# micro_power.net
KiCad netlist of a schematic drawn in Altium Designer
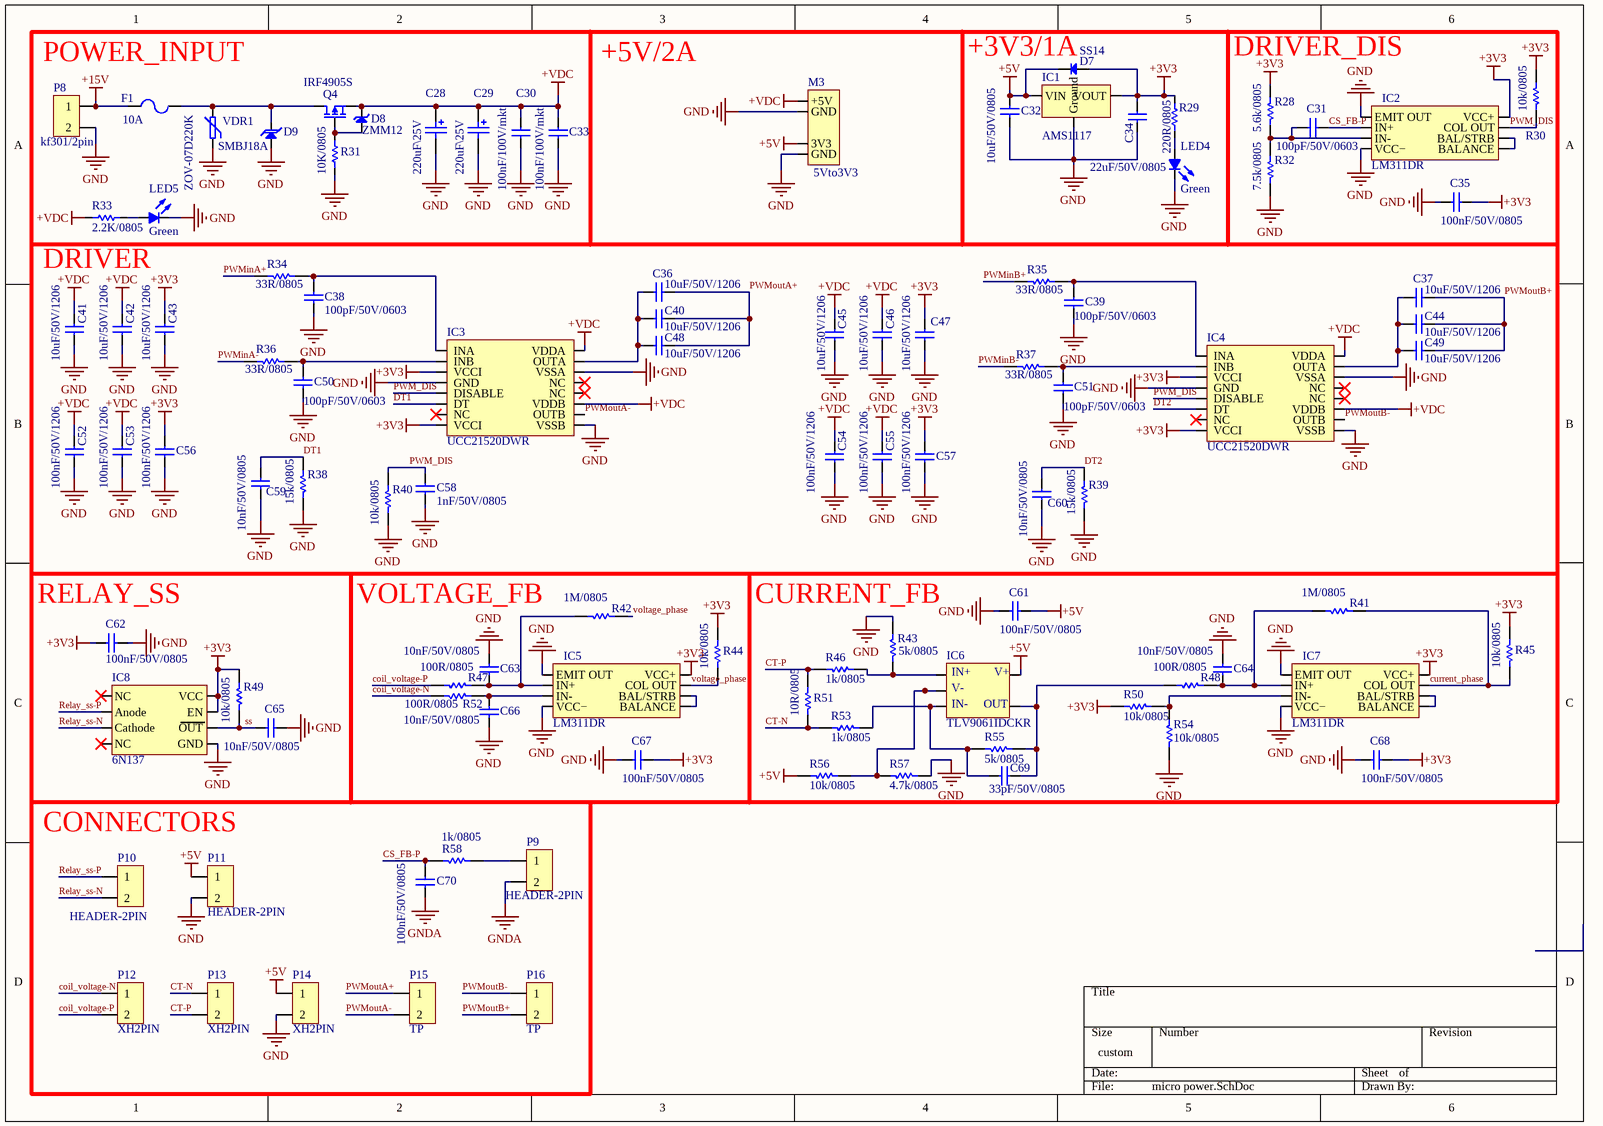
[diagram p0: micro power.SchDoc]

(export (version "E")
  (design (tool "Eeschema 10.0.6"))
  (components
    (comp (ref "C28")
      (value "220u~{F}25V")
      (footprint "cap 5*11,p=2")
      (description "Polarized Capacitor (Radial)")
      (fields (field (name "PUBLISHER") "Altium Limited"))
      (libsource (lib "Schlib") (part "Cap Pol1"))
    )
    (comp (ref "C29")
      (value "220u~{F}25V")
      (footprint "cap 5*11,p=2")
      (description "Polarized Capacitor (Radial)")
      (fields (field (name "PUBLISHER") "Altium Limited"))
      (libsource (lib "Schlib") (part "Cap Pol1"))
    )
    (comp (ref "C30")
      (value "100nF/100V/mkt")
      (footprint "mkt 5mm")
      (description "Capacitor")
      (libsource (lib "Schlib") (part "Capacitor"))
    )
    (comp (ref "C31")
      (value "100pF/50V/0603")
      (footprint "cap 0603")
      (description "Capacitor")
      (libsource (lib "Schlib") (part "Capacitor"))
    )
    (comp (ref "C32")
      (value "10uF/50V/0805")
      (footprint "CAP 0805")
      (description "Capacitor")
      (libsource (lib "Schlib") (part "Capacitor"))
    )
    (comp (ref "C33")
      (value "100nF/100V/mkt")
      (footprint "mkt 5mm")
      (description "Capacitor")
      (libsource (lib "Schlib") (part "Capacitor"))
    )
    (comp (ref "C34")
      (value "22uF/50V/0805")
      (footprint "CAP 0805")
      (description "Capacitor")
      (libsource (lib "Schlib") (part "Capacitor"))
    )
    (comp (ref "C35")
      (value "100nF/50V/0805")
      (footprint "CAP 0805")
      (description "Capacitor")
      (libsource (lib "Schlib") (part "Capacitor"))
    )
    (comp (ref "C36")
      (value "10uF/50V/1206")
      (footprint "CAP 1206")
      (description "Capacitor")
      (libsource (lib "Schlib") (part "Capacitor"))
    )
    (comp (ref "C37")
      (value "10uF/50V/1206")
      (footprint "CAP 1206")
      (description "Capacitor")
      (libsource (lib "Schlib") (part "Capacitor"))
    )
    (comp (ref "C38")
      (value "100pF/50V/0603")
      (footprint "cap 0603")
      (description "Capacitor")
      (libsource (lib "Schlib") (part "Capacitor"))
    )
    (comp (ref "C39")
      (value "100pF/50V/0603")
      (footprint "cap 0603")
      (description "Capacitor")
      (libsource (lib "Schlib") (part "Capacitor"))
    )
    (comp (ref "C40")
      (value "10uF/50V/1206")
      (footprint "CAP 1206")
      (description "Capacitor")
      (libsource (lib "Schlib") (part "Capacitor"))
    )
    (comp (ref "C41")
      (value "10uF/50V/1206")
      (footprint "CAP 1206")
      (description "Capacitor")
      (libsource (lib "Schlib") (part "Capacitor"))
    )
    (comp (ref "C42")
      (value "10uF/50V/1206")
      (footprint "CAP 1206")
      (description "Capacitor")
      (libsource (lib "Schlib") (part "Capacitor"))
    )
    (comp (ref "C43")
      (value "10uF/50V/1206")
      (footprint "CAP 1206")
      (description "Capacitor")
      (libsource (lib "Schlib") (part "Capacitor"))
    )
    (comp (ref "C44")
      (value "10uF/50V/1206")
      (footprint "CAP 1206")
      (description "Capacitor")
      (libsource (lib "Schlib") (part "Capacitor"))
    )
    (comp (ref "C45")
      (value "10uF/50V/1206")
      (footprint "CAP 1206")
      (description "Capacitor")
      (libsource (lib "Schlib") (part "Capacitor"))
    )
    (comp (ref "C46")
      (value "10uF/50V/1206")
      (footprint "CAP 1206")
      (description "Capacitor")
      (libsource (lib "Schlib") (part "Capacitor"))
    )
    (comp (ref "C47")
      (value "10uF/50V/1206")
      (footprint "CAP 1206")
      (description "Capacitor")
      (libsource (lib "Schlib") (part "Capacitor"))
    )
    (comp (ref "C48")
      (value "10uF/50V/1206")
      (footprint "CAP 1206")
      (description "Capacitor")
      (libsource (lib "Schlib") (part "Capacitor"))
    )
    (comp (ref "C49")
      (value "10uF/50V/1206")
      (footprint "CAP 1206")
      (description "Capacitor")
      (libsource (lib "Schlib") (part "Capacitor"))
    )
    (comp (ref "C50")
      (value "100pF/50V/0603")
      (footprint "cap 0603")
      (description "Capacitor")
      (libsource (lib "Schlib") (part "Capacitor"))
    )
    (comp (ref "C51")
      (value "100pF/50V/0603")
      (footprint "cap 0603")
      (description "Capacitor")
      (libsource (lib "Schlib") (part "Capacitor"))
    )
    (comp (ref "C52")
      (value "100nF/50V/1206")
      (footprint "CAP 1206")
      (description "Capacitor")
      (libsource (lib "Schlib") (part "Capacitor"))
    )
    (comp (ref "C53")
      (value "100nF/50V/1206")
      (footprint "CAP 1206")
      (description "Capacitor")
      (libsource (lib "Schlib") (part "Capacitor"))
    )
    (comp (ref "C54")
      (value "100nF/50V/1206")
      (footprint "CAP 1206")
      (description "Capacitor")
      (libsource (lib "Schlib") (part "Capacitor"))
    )
    (comp (ref "C55")
      (value "100nF/50V/1206")
      (footprint "CAP 1206")
      (description "Capacitor")
      (libsource (lib "Schlib") (part "Capacitor"))
    )
    (comp (ref "C56")
      (value "100nF/50V/1206")
      (footprint "CAP 1206")
      (description "Capacitor")
      (libsource (lib "Schlib") (part "Capacitor"))
    )
    (comp (ref "C57")
      (value "100nF/50V/1206")
      (footprint "CAP 1206")
      (description "Capacitor")
      (libsource (lib "Schlib") (part "Capacitor"))
    )
    (comp (ref "C58")
      (value "1nF/50V/0805")
      (footprint "CAP 0805")
      (description "Capacitor")
      (libsource (lib "Schlib") (part "Capacitor"))
    )
    (comp (ref "C59")
      (value "10nF/50V/0805")
      (footprint "CAP 0805")
      (description "Capacitor")
      (libsource (lib "Schlib") (part "Capacitor"))
    )
    (comp (ref "C60")
      (value "10nF/50V/0805")
      (footprint "CAP 0805")
      (description "Capacitor")
      (libsource (lib "Schlib") (part "Capacitor"))
    )
    (comp (ref "C61")
      (value "100nF/50V/0805")
      (footprint "CAP 0805")
      (description "Capacitor")
      (libsource (lib "Schlib") (part "Capacitor"))
    )
    (comp (ref "C62")
      (value "100nF/50V/0805")
      (footprint "CAP 0805")
      (description "Capacitor")
      (libsource (lib "Schlib") (part "Capacitor"))
    )
    (comp (ref "C63")
      (value "10nF/50V/0805")
      (footprint "CAP 0805")
      (description "Capacitor")
      (libsource (lib "Schlib") (part "Capacitor"))
    )
    (comp (ref "C64")
      (value "10nF/50V/0805")
      (footprint "CAP 0805")
      (description "Capacitor")
      (libsource (lib "Schlib") (part "Capacitor"))
    )
    (comp (ref "C65")
      (value "10nF/50V/0805")
      (footprint "CAP 0805")
      (description "Capacitor")
      (libsource (lib "Schlib") (part "Capacitor"))
    )
    (comp (ref "C66")
      (value "10nF/50V/0805")
      (footprint "CAP 0805")
      (description "Capacitor")
      (libsource (lib "Schlib") (part "Capacitor"))
    )
    (comp (ref "C67")
      (value "100nF/50V/0805")
      (footprint "CAP 0805")
      (description "Capacitor")
      (libsource (lib "Schlib") (part "Capacitor"))
    )
    (comp (ref "C68")
      (value "100nF/50V/0805")
      (footprint "CAP 0805")
      (description "Capacitor")
      (libsource (lib "Schlib") (part "Capacitor"))
    )
    (comp (ref "C69")
      (value "33pF/50V/0805")
      (footprint "CAP 0805")
      (description "Capacitor")
      (libsource (lib "Schlib") (part "Capacitor"))
    )
    (comp (ref "C70")
      (value "100nF/50V/0805")
      (footprint "CAP 0805")
      (description "Capacitor")
      (libsource (lib "Schlib") (part "Capacitor"))
    )
    (comp (ref "D7") (value "SS14") (footprint "SMA") (libsource (lib "Schlib") (part "Diode")))
    (comp (ref "D8") (value "ZMM12") (footprint "minimelf") (libsource (lib "Schlib") (part "ZENER")))
    (comp (ref "D9")
      (value "SMBJ18A")
      (footprint "SMB(DO-214AA)")
      (libsource (lib "Schlib") (part "TVS_Unidirectional"))
    )
    (comp (ref "F1")
      (value "10A")
      (footprint "smd Fuse Block 155 OMNI-BLOK")
      (description "Fuse")
      (libsource (lib "Fx7sam") (part "Fuse"))
    )
    (comp (ref "IC1")
      (value "AMS1117")
      (footprint "TO252 (DPAK) (Type TH)")
      (libsource (lib "Schlib") (part "AMS1117"))
    )
    (comp (ref "IC2") (value "LM311DR") (footprint "SOIC-8") (libsource (lib "Schlib") (part "LM311DR")))
    (comp (ref "IC3")
      (value "UCC21520DWR")
      (footprint "SOIC16W")
      (libsource (lib "Schlib") (part "UCC21520DWR"))
    )
    (comp (ref "IC4")
      (value "UCC21520DWR")
      (footprint "SOIC16W")
      (libsource (lib "Schlib") (part "UCC21520DWR"))
    )
    (comp (ref "IC5") (value "LM311DR") (footprint "SOIC-8") (libsource (lib "Schlib") (part "LM311DR")))
    (comp (ref "IC6")
      (value "TLV9061IDCKR")
      (footprint "SC70-5")
      (libsource (lib "Schlib") (part "TLV9061IDCKR"))
    )
    (comp (ref "IC7") (value "LM311DR") (footprint "SOIC-8") (libsource (lib "Schlib") (part "LM311DR")))
    (comp (ref "IC8") (value "6N137") (footprint "SMD-8 Gull Wing") (libsource (lib "Schlib") (part "6N137")))
    (comp (ref "LED4")
      (value "LED 3mm/Green")
      (footprint "LED 3mm")
      (description "Typical LED")
      (fields (field (name "COLOR") "Green"))
      (libsource (lib "TL494 12V-20A-KARA") (part "LED"))
    )
    (comp (ref "LED5")
      (value "LED 3mm/Green")
      (footprint "LED 3mm")
      (description "Typical LED")
      (fields (field (name "COLOR") "Green"))
      (libsource (lib "TL494 12V-20A-KARA") (part "LED"))
    )
    (comp (ref "M3") (value "5Vto3V3") (footprint "5Vto3V3") (libsource (lib "Schlib") (part "5Vto3V3")))
    (comp (ref "P8")
      (value "kf301/2pin")
      (footprint "KF301-5.0-2P")
      (description "RELAY")
      (fields (field (name "PUBLISHER") "Altium Limited"))
      (libsource (lib "") (part "Header 2H_1"))
    )
    (comp (ref "P9")
      (value "HEADER-2PIN")
      (footprint "pin-header 2*1")
      (description "RELAY")
      (fields (field (name "PUBLISHER") "Altium Limited"))
      (libsource (lib "Schlib") (part "Header 2H"))
    )
    (comp (ref "P10")
      (value "HEADER-2PIN")
      (footprint "XH-2Pin")
      (description "RELAY")
      (fields (field (name "PUBLISHER") "Altium Limited"))
      (libsource (lib "Schlib") (part "Header 2H"))
    )
    (comp (ref "P11")
      (value "HEADER-2PIN")
      (footprint "pin-header 2*1")
      (description "RELAY")
      (fields (field (name "PUBLISHER") "Altium Limited"))
      (libsource (lib "Schlib") (part "Header 2H"))
    )
    (comp (ref "P12")
      (value "XH2PIN")
      (footprint "XH-2Pin")
      (description "RELAY")
      (fields (field (name "PUBLISHER") "Altium Limited"))
      (libsource (lib "Schlib") (part "Header 2H"))
    )
    (comp (ref "P13")
      (value "XH2PIN")
      (footprint "XH-2Pin")
      (description "RELAY")
      (fields (field (name "PUBLISHER") "Altium Limited"))
      (libsource (lib "Schlib") (part "Header 2H"))
    )
    (comp (ref "P14")
      (value "XH2PIN")
      (footprint "XH-2Pin")
      (description "RELAY")
      (fields (field (name "PUBLISHER") "Altium Limited"))
      (libsource (lib "Schlib") (part "Header 2H"))
    )
    (comp (ref "P15")
      (value "TP")
      (footprint "puls")
      (description "RELAY")
      (fields (field (name "PUBLISHER") "Altium Limited"))
      (libsource (lib "Schlib") (part "Header 2H"))
    )
    (comp (ref "P16")
      (value "TP")
      (footprint "puls")
      (description "RELAY")
      (fields (field (name "PUBLISHER") "Altium Limited"))
      (libsource (lib "Schlib") (part "Header 2H"))
    )
    (comp (ref "Q4")
      (value "IRF4905S")
      (footprint "TO263AB (D2PAK)")
      (description "D2pak")
      (libsource (lib "Schlib") (part "Mosfet P-channel"))
    )
    (comp (ref "R28")
      (value "5.6k/0805")
      (footprint "RES 0805")
      (description "Resistor")
      (fields (field (name "PUBLISHER") "Altium Limited"))
      (libsource (lib "Miscellaneous Devices") (part "Res1"))
    )
    (comp (ref "R29") (value "220R/0805") (footprint "RES 0805") (libsource (lib "Schlib") (part "Res")))
    (comp (ref "R30")
      (value "10k/0805")
      (footprint "RES 0805")
      (description "Resistor")
      (fields (field (name "PUBLISHER") "Altium Limited"))
      (libsource (lib "Miscellaneous Devices") (part "Res1"))
    )
    (comp (ref "R31") (value "10K/0805") (footprint "RES 0805") (libsource (lib "Schlib") (part "Res")))
    (comp (ref "R32")
      (value "7.5k/0805")
      (footprint "RES 0805")
      (description "Resistor")
      (fields (field (name "PUBLISHER") "Altium Limited"))
      (libsource (lib "Miscellaneous Devices") (part "Res1"))
    )
    (comp (ref "R33") (value "2.2K/0805") (footprint "RES 0805") (libsource (lib "Schlib") (part "Res")))
    (comp (ref "R34")
      (value "33R/0805")
      (footprint "RES 0805")
      (description "Resistor")
      (fields (field (name "PUBLISHER") "Altium Limited"))
      (libsource (lib "Miscellaneous Devices") (part "Res1"))
    )
    (comp (ref "R35")
      (value "33R/0805")
      (footprint "RES 0805")
      (description "Resistor")
      (fields (field (name "PUBLISHER") "Altium Limited"))
      (libsource (lib "Miscellaneous Devices") (part "Res1"))
    )
    (comp (ref "R36")
      (value "33R/0805")
      (footprint "RES 0805")
      (description "Resistor")
      (fields (field (name "PUBLISHER") "Altium Limited"))
      (libsource (lib "Miscellaneous Devices") (part "Res1"))
    )
    (comp (ref "R37")
      (value "33R/0805")
      (footprint "RES 0805")
      (description "Resistor")
      (fields (field (name "PUBLISHER") "Altium Limited"))
      (libsource (lib "Miscellaneous Devices") (part "Res1"))
    )
    (comp (ref "R38")
      (value "15k/0805")
      (footprint "RES 0805")
      (description "Resistor")
      (fields (field (name "PUBLISHER") "Altium Limited"))
      (libsource (lib "Miscellaneous Devices") (part "Res1"))
    )
    (comp (ref "R39")
      (value "15k/0805")
      (footprint "RES 0805")
      (description "Resistor")
      (fields (field (name "PUBLISHER") "Altium Limited"))
      (libsource (lib "Miscellaneous Devices") (part "Res1"))
    )
    (comp (ref "R40")
      (value "10k/0805")
      (footprint "RES 0805")
      (description "Resistor")
      (fields (field (name "PUBLISHER") "Altium Limited"))
      (libsource (lib "Miscellaneous Devices") (part "Res1"))
    )
    (comp (ref "R41")
      (value "1M/0805")
      (footprint "RES 0805")
      (description "Resistor")
      (fields (field (name "PUBLISHER") "Altium Limited"))
      (libsource (lib "Miscellaneous Devices") (part "Res1"))
    )
    (comp (ref "R42")
      (value "1M/0805")
      (footprint "RES 0805")
      (description "Resistor")
      (fields (field (name "PUBLISHER") "Altium Limited"))
      (libsource (lib "Miscellaneous Devices") (part "Res1"))
    )
    (comp (ref "R43")
      (value "5k/0805")
      (footprint "RES 0805")
      (description "Resistor")
      (fields (field (name "PUBLISHER") "Altium Limited"))
      (libsource (lib "Miscellaneous Devices") (part "Res1"))
    )
    (comp (ref "R44")
      (value "10k/0805")
      (footprint "RES 0805")
      (description "Resistor")
      (fields (field (name "PUBLISHER") "Altium Limited"))
      (libsource (lib "Miscellaneous Devices") (part "Res1"))
    )
    (comp (ref "R45")
      (value "10k/0805")
      (footprint "RES 0805")
      (description "Resistor")
      (fields (field (name "PUBLISHER") "Altium Limited"))
      (libsource (lib "Miscellaneous Devices") (part "Res1"))
    )
    (comp (ref "R46")
      (value "1k/0805")
      (footprint "RES 0805")
      (description "Resistor")
      (fields (field (name "PUBLISHER") "Altium Limited"))
      (libsource (lib "Miscellaneous Devices") (part "Res1"))
    )
    (comp (ref "R47")
      (value "100R/0805")
      (footprint "RES 0805")
      (description "Resistor")
      (fields (field (name "PUBLISHER") "Altium Limited"))
      (libsource (lib "Miscellaneous Devices") (part "Res1"))
    )
    (comp (ref "R48")
      (value "100R/0805")
      (footprint "RES 0805")
      (description "Resistor")
      (fields (field (name "PUBLISHER") "Altium Limited"))
      (libsource (lib "Miscellaneous Devices") (part "Res1"))
    )
    (comp (ref "R49")
      (value "10k/0805")
      (footprint "RES 0805")
      (description "Resistor")
      (fields (field (name "PUBLISHER") "Altium Limited"))
      (libsource (lib "Miscellaneous Devices") (part "Res1"))
    )
    (comp (ref "R50")
      (value "10k/0805")
      (footprint "RES 0805")
      (description "Resistor")
      (fields (field (name "PUBLISHER") "Altium Limited"))
      (libsource (lib "Miscellaneous Devices") (part "Res1"))
    )
    (comp (ref "R51")
      (value "10R/0805")
      (footprint "RES 0805")
      (description "Resistor")
      (fields (field (name "PUBLISHER") "Altium Limited"))
      (libsource (lib "Miscellaneous Devices") (part "Res1"))
    )
    (comp (ref "R52")
      (value "100R/0805")
      (footprint "RES 0805")
      (description "Resistor")
      (fields (field (name "PUBLISHER") "Altium Limited"))
      (libsource (lib "Miscellaneous Devices") (part "Res1"))
    )
    (comp (ref "R53")
      (value "1k/0805")
      (footprint "RES 0805")
      (description "Resistor")
      (fields (field (name "PUBLISHER") "Altium Limited"))
      (libsource (lib "Miscellaneous Devices") (part "Res1"))
    )
    (comp (ref "R54")
      (value "10k/0805")
      (footprint "RES 0805")
      (description "Resistor")
      (fields (field (name "PUBLISHER") "Altium Limited"))
      (libsource (lib "Miscellaneous Devices") (part "Res1"))
    )
    (comp (ref "R55")
      (value "5k/0805")
      (footprint "RES 0805")
      (description "Resistor")
      (fields (field (name "PUBLISHER") "Altium Limited"))
      (libsource (lib "Miscellaneous Devices") (part "Res1"))
    )
    (comp (ref "R56")
      (value "10k/0805")
      (footprint "RES 0805")
      (description "Resistor")
      (fields (field (name "PUBLISHER") "Altium Limited"))
      (libsource (lib "Miscellaneous Devices") (part "Res1"))
    )
    (comp (ref "R57")
      (value "4.7k/0805")
      (footprint "RES 0805")
      (description "Resistor")
      (fields (field (name "PUBLISHER") "Altium Limited"))
      (libsource (lib "Miscellaneous Devices") (part "Res1"))
    )
    (comp (ref "R58")
      (value "1k/0805")
      (footprint "RES 0805")
      (description "Resistor")
      (fields (field (name "PUBLISHER") "Altium Limited"))
      (libsource (lib "Miscellaneous Devices") (part "Res1"))
    )
    (comp (ref "VDR1")
      (value "ZOV-07D220K")
      (footprint "7D471K")
      (description "VARISTORS")
      (fields
        (field (name "MANUFACTURER") "china-canada-philipina")
        (field (name "DESIGNER") "Abbas Basereh")
        (field (name "PUBLISHER") "ABBAS BASEREH")
      )
      (libsource (lib "Schlib") (part "VARISTOR (VDR)"))
    )
  )
  (nets
    (net (code "1") (name "+3V3") (class "Default")
      (node (ref "C34") (pin "1") (pinfunction "+_1") (pintype "passive"))
      (node (ref "C35") (pin "1") (pinfunction "+_1") (pintype "passive"))
      (node (ref "C43") (pin "2") (pinfunction "-_2") (pintype "passive"))
      (node (ref "C47") (pin "2") (pinfunction "-_2") (pintype "passive"))
      (node (ref "C56") (pin "2") (pinfunction "-_2") (pintype "passive"))
      (node (ref "C57") (pin "2") (pinfunction "-_2") (pintype "passive"))
      (node (ref "C62") (pin "1") (pinfunction "+_1") (pintype "passive"))
      (node (ref "C67") (pin "1") (pinfunction "+_1") (pintype "passive"))
      (node (ref "C68") (pin "1") (pinfunction "+_1") (pintype "passive"))
      (node (ref "D7") (pin "1") (pinfunction "1_1") (pintype "passive"))
      (node (ref "IC1") (pin "2") (pinfunction "VOUT_2") (pintype "passive"))
      (node (ref "IC2") (pin "8") (pinfunction "VCC+_8") (pintype "passive"))
      (node (ref "IC3") (pin "3") (pinfunction "VCCI_3") (pintype "passive"))
      (node (ref "IC3") (pin "8") (pinfunction "VCCI_8") (pintype "passive"))
      (node (ref "IC4") (pin "3") (pinfunction "VCCI_3") (pintype "passive"))
      (node (ref "IC4") (pin "8") (pinfunction "VCCI_8") (pintype "passive"))
      (node (ref "IC5") (pin "8") (pinfunction "VCC+_8") (pintype "passive"))
      (node (ref "IC7") (pin "8") (pinfunction "VCC+_8") (pintype "passive"))
      (node (ref "IC8") (pin "7") (pinfunction "EN_7") (pintype "passive"))
      (node (ref "IC8") (pin "8") (pinfunction "VCC_8") (pintype "passive"))
      (node (ref "R28") (pin "2") (pinfunction "2_2") (pintype "passive"))
      (node (ref "R29") (pin "2") (pinfunction "2_2") (pintype "passive"))
      (node (ref "R30") (pin "2") (pinfunction "2_2") (pintype "passive"))
      (node (ref "R44") (pin "2") (pinfunction "2_2") (pintype "passive"))
      (node (ref "R45") (pin "2") (pinfunction "2_2") (pintype "passive"))
      (node (ref "R49") (pin "2") (pinfunction "2_2") (pintype "passive"))
      (node (ref "R50") (pin "2") (pinfunction "2_2") (pintype "passive"))
    )
    (net (code "2") (name "+5V") (class "Default")
      (node (ref "C32") (pin "1") (pinfunction "+_1") (pintype "passive"))
      (node (ref "C61") (pin "1") (pinfunction "+_1") (pintype "passive"))
      (node (ref "D7") (pin "2") (pinfunction "2_2") (pintype "passive"))
      (node (ref "IC1") (pin "3") (pinfunction "VIN_3") (pintype "passive"))
      (node (ref "IC6") (pin "5") (pinfunction "5_5") (pintype "passive"))
      (node (ref "M3") (pin "3") (pinfunction "3V3_3") (pintype "passive"))
      (node (ref "P11") (pin "1") (pinfunction "1_1") (pintype "passive"))
      (node (ref "P14") (pin "1") (pinfunction "1_1") (pintype "passive"))
      (node (ref "R56") (pin "1") (pinfunction "1_1") (pintype "passive"))
    )
    (net (code "3") (name "+15V") (class "Default")
      (node (ref "F1") (pin "1") (pinfunction "1_1") (pintype "passive"))
      (node (ref "P8") (pin "1") (pinfunction "1_1") (pintype "passive"))
    )
    (net (code "4") (name "+VDC") (class "Default")
      (node (ref "C28") (pin "1") (pinfunction "1_1") (pintype "passive"))
      (node (ref "C29") (pin "1") (pinfunction "1_1") (pintype "passive"))
      (node (ref "C30") (pin "1") (pinfunction "+_1") (pintype "passive"))
      (node (ref "C33") (pin "1") (pinfunction "+_1") (pintype "passive"))
      (node (ref "C41") (pin "2") (pinfunction "-_2") (pintype "passive"))
      (node (ref "C42") (pin "2") (pinfunction "-_2") (pintype "passive"))
      (node (ref "C45") (pin "2") (pinfunction "-_2") (pintype "passive"))
      (node (ref "C46") (pin "2") (pinfunction "-_2") (pintype "passive"))
      (node (ref "C52") (pin "2") (pinfunction "-_2") (pintype "passive"))
      (node (ref "C53") (pin "2") (pinfunction "-_2") (pintype "passive"))
      (node (ref "C54") (pin "2") (pinfunction "-_2") (pintype "passive"))
      (node (ref "C55") (pin "2") (pinfunction "-_2") (pintype "passive"))
      (node (ref "D8") (pin "2") (pinfunction "K_2") (pintype "passive"))
      (node (ref "IC3") (pin "11") (pinfunction "VDDB_11") (pintype "passive"))
      (node (ref "IC3") (pin "16") (pinfunction "VDDA_16") (pintype "passive"))
      (node (ref "IC4") (pin "11") (pinfunction "VDDB_11") (pintype "passive"))
      (node (ref "IC4") (pin "16") (pinfunction "VDDA_16") (pintype "passive"))
      (node (ref "M3") (pin "1") (pinfunction "+5V_1") (pintype "passive"))
      (node (ref "Q4") (pin "3") (pinfunction "S_3") (pintype "passive"))
      (node (ref "R33") (pin "2") (pinfunction "2_2") (pintype "passive"))
    )
    (net (code "5") (name "/CS_FB-P") (class "Default")
      (node (ref "C31") (pin "2") (pinfunction "-_2") (pintype "passive"))
      (node (ref "C70") (pin "1") (pinfunction "+_1") (pintype "passive"))
      (node (ref "IC2") (pin "2") (pinfunction "IN+_2") (pintype "passive"))
      (node (ref "R58") (pin "2") (pinfunction "2_2") (pintype "passive"))
    )
    (net (code "6") (name "/CT-N") (class "Default")
      (node (ref "P13") (pin "1") (pinfunction "1_1") (pintype "passive"))
      (node (ref "R51") (pin "1") (pinfunction "1_1") (pintype "passive"))
      (node (ref "R53") (pin "2") (pinfunction "2_2") (pintype "passive"))
    )
    (net (code "7") (name "/CT-P") (class "Default")
      (node (ref "P13") (pin "2") (pinfunction "2_2") (pintype "passive"))
      (node (ref "R46") (pin "2") (pinfunction "2_2") (pintype "passive"))
      (node (ref "R51") (pin "2") (pinfunction "2_2") (pintype "passive"))
    )
    (net (code "8") (name "/DT1") (class "Default")
      (node (ref "C59") (pin "2") (pinfunction "-_2") (pintype "passive"))
      (node (ref "IC3") (pin "6") (pinfunction "DT_6") (pintype "passive"))
      (node (ref "R38") (pin "1") (pinfunction "1_1") (pintype "passive"))
    )
    (net (code "9") (name "/DT2") (class "Default")
      (node (ref "C60") (pin "2") (pinfunction "-_2") (pintype "passive"))
      (node (ref "IC4") (pin "6") (pinfunction "DT_6") (pintype "passive"))
      (node (ref "R39") (pin "1") (pinfunction "1_1") (pintype "passive"))
    )
    (net (code "10") (name "/PWM_DIS") (class "Default")
      (node (ref "C58") (pin "2") (pinfunction "-_2") (pintype "passive"))
      (node (ref "IC2") (pin "7") (pinfunction "COL_OUT_7") (pintype "passive"))
      (node (ref "IC3") (pin "5") (pinfunction "DISABLE_5") (pintype "passive"))
      (node (ref "IC4") (pin "5") (pinfunction "DISABLE_5") (pintype "passive"))
      (node (ref "R30") (pin "1") (pinfunction "1_1") (pintype "passive"))
      (node (ref "R40") (pin "2") (pinfunction "2_2") (pintype "passive"))
    )
    (net (code "11") (name "/PWMinA+") (class "Default")
      (node (ref "R34") (pin "2") (pinfunction "2_2") (pintype "passive"))
    )
    (net (code "12") (name "/PWMinA-") (class "Default")
      (node (ref "R36") (pin "2") (pinfunction "2_2") (pintype "passive"))
    )
    (net (code "13") (name "/PWMinB+") (class "Default")
      (node (ref "R35") (pin "2") (pinfunction "2_2") (pintype "passive"))
    )
    (net (code "14") (name "/PWMinB-") (class "Default")
      (node (ref "R37") (pin "2") (pinfunction "2_2") (pintype "passive"))
    )
    (net (code "15") (name "/PWMoutA+") (class "Default")
      (node (ref "C36") (pin "2") (pinfunction "-_2") (pintype "passive"))
      (node (ref "C40") (pin "2") (pinfunction "-_2") (pintype "passive"))
      (node (ref "C48") (pin "1") (pinfunction "+_1") (pintype "passive"))
      (node (ref "P15") (pin "1") (pinfunction "1_1") (pintype "passive"))
    )
    (net (code "16") (name "/PWMoutA-") (class "Default")
      (node (ref "IC3") (pin "10") (pinfunction "OUTB_10") (pintype "passive"))
      (node (ref "P15") (pin "2") (pinfunction "2_2") (pintype "passive"))
    )
    (net (code "17") (name "/PWMoutB+") (class "Default")
      (node (ref "C37") (pin "2") (pinfunction "-_2") (pintype "passive"))
      (node (ref "C44") (pin "2") (pinfunction "-_2") (pintype "passive"))
      (node (ref "C49") (pin "1") (pinfunction "+_1") (pintype "passive"))
      (node (ref "P16") (pin "2") (pinfunction "2_2") (pintype "passive"))
    )
    (net (code "18") (name "/PWMoutB-") (class "Default")
      (node (ref "IC4") (pin "10") (pinfunction "OUTB_10") (pintype "passive"))
      (node (ref "P16") (pin "1") (pinfunction "1_1") (pintype "passive"))
    )
    (net (code "19") (name "/Relay_ss-N") (class "Default")
      (node (ref "IC8") (pin "3") (pinfunction "Cathode_3") (pintype "passive"))
      (node (ref "P10") (pin "2") (pinfunction "2_2") (pintype "passive"))
    )
    (net (code "20") (name "/Relay_ss-P") (class "Default")
      (node (ref "IC8") (pin "2") (pinfunction "Anode_2") (pintype "passive"))
      (node (ref "P10") (pin "1") (pinfunction "1_1") (pintype "passive"))
    )
    (net (code "21") (name "/coil_voltage-N") (class "Default")
      (node (ref "P12") (pin "1") (pinfunction "1_1") (pintype "passive"))
      (node (ref "R52") (pin "2") (pinfunction "2_2") (pintype "passive"))
    )
    (net (code "22") (name "/coil_voltage-P") (class "Default")
      (node (ref "P12") (pin "2") (pinfunction "2_2") (pintype "passive"))
      (node (ref "R47") (pin "2") (pinfunction "2_2") (pintype "passive"))
    )
    (net (code "23") (name "/current_phase") (class "Default")
      (node (ref "IC7") (pin "7") (pinfunction "COL_OUT_7") (pintype "passive"))
      (node (ref "R41") (pin "1") (pinfunction "1_1") (pintype "passive"))
      (node (ref "R45") (pin "1") (pinfunction "1_1") (pintype "passive"))
    )
    (net (code "24") (name "/ss") (class "Default")
      (node (ref "C65") (pin "2") (pinfunction "-_2") (pintype "passive"))
      (node (ref "IC8") (pin "6") (pinfunction "OUT_6") (pintype "passive"))
      (node (ref "R49") (pin "1") (pinfunction "1_1") (pintype "passive"))
    )
    (net (code "25") (name "/voltage_phase") (class "Default")
      (node (ref "IC5") (pin "7") (pinfunction "COL_OUT_7") (pintype "passive"))
      (node (ref "R42") (pin "1") (pinfunction "1_1") (pintype "passive"))
      (node (ref "R44") (pin "1") (pinfunction "1_1") (pintype "passive"))
    )
    (net (code "26") (name "GND") (class "Default")
      (node (ref "C28") (pin "2") (pinfunction "2_2") (pintype "passive"))
      (node (ref "C29") (pin "2") (pinfunction "2_2") (pintype "passive"))
      (node (ref "C30") (pin "2") (pinfunction "-_2") (pintype "passive"))
      (node (ref "C32") (pin "2") (pinfunction "-_2") (pintype "passive"))
      (node (ref "C33") (pin "2") (pinfunction "-_2") (pintype "passive"))
      (node (ref "C34") (pin "2") (pinfunction "-_2") (pintype "passive"))
      (node (ref "C35") (pin "2") (pinfunction "-_2") (pintype "passive"))
      (node (ref "C38") (pin "2") (pinfunction "-_2") (pintype "passive"))
      (node (ref "C39") (pin "2") (pinfunction "-_2") (pintype "passive"))
      (node (ref "C41") (pin "1") (pinfunction "+_1") (pintype "passive"))
      (node (ref "C42") (pin "1") (pinfunction "+_1") (pintype "passive"))
      (node (ref "C43") (pin "1") (pinfunction "+_1") (pintype "passive"))
      (node (ref "C45") (pin "1") (pinfunction "+_1") (pintype "passive"))
      (node (ref "C46") (pin "1") (pinfunction "+_1") (pintype "passive"))
      (node (ref "C47") (pin "1") (pinfunction "+_1") (pintype "passive"))
      (node (ref "C50") (pin "2") (pinfunction "-_2") (pintype "passive"))
      (node (ref "C51") (pin "2") (pinfunction "-_2") (pintype "passive"))
      (node (ref "C52") (pin "1") (pinfunction "+_1") (pintype "passive"))
      (node (ref "C53") (pin "1") (pinfunction "+_1") (pintype "passive"))
      (node (ref "C54") (pin "1") (pinfunction "+_1") (pintype "passive"))
      (node (ref "C55") (pin "1") (pinfunction "+_1") (pintype "passive"))
      (node (ref "C56") (pin "1") (pinfunction "+_1") (pintype "passive"))
      (node (ref "C57") (pin "1") (pinfunction "+_1") (pintype "passive"))
      (node (ref "C58") (pin "1") (pinfunction "+_1") (pintype "passive"))
      (node (ref "C59") (pin "1") (pinfunction "+_1") (pintype "passive"))
      (node (ref "C60") (pin "1") (pinfunction "+_1") (pintype "passive"))
      (node (ref "C61") (pin "2") (pinfunction "-_2") (pintype "passive"))
      (node (ref "C62") (pin "2") (pinfunction "-_2") (pintype "passive"))
      (node (ref "C63") (pin "1") (pinfunction "+_1") (pintype "passive"))
      (node (ref "C64") (pin "1") (pinfunction "+_1") (pintype "passive"))
      (node (ref "C65") (pin "1") (pinfunction "+_1") (pintype "passive"))
      (node (ref "C66") (pin "2") (pinfunction "-_2") (pintype "passive"))
      (node (ref "C67") (pin "2") (pinfunction "-_2") (pintype "passive"))
      (node (ref "C68") (pin "2") (pinfunction "-_2") (pintype "passive"))
      (node (ref "D9") (pin "1") (pinfunction "1_1") (pintype "passive"))
      (node (ref "IC1") (pin "1") (pinfunction "Ground_1") (pintype "passive"))
      (node (ref "IC2") (pin "1") (pinfunction "EMIT_OUT_1") (pintype "passive"))
      (node (ref "IC2") (pin "4") (pinfunction "VCC−_4") (pintype "passive"))
      (node (ref "IC3") (pin "14") (pinfunction "VSSA_14") (pintype "passive"))
      (node (ref "IC3") (pin "4") (pinfunction "GND_4") (pintype "passive"))
      (node (ref "IC3") (pin "9") (pinfunction "VSSB_9") (pintype "passive"))
      (node (ref "IC4") (pin "14") (pinfunction "VSSA_14") (pintype "passive"))
      (node (ref "IC4") (pin "4") (pinfunction "GND_4") (pintype "passive"))
      (node (ref "IC4") (pin "9") (pinfunction "VSSB_9") (pintype "passive"))
      (node (ref "IC5") (pin "1") (pinfunction "EMIT_OUT_1") (pintype "passive"))
      (node (ref "IC5") (pin "4") (pinfunction "VCC−_4") (pintype "passive"))
      (node (ref "IC7") (pin "1") (pinfunction "EMIT_OUT_1") (pintype "passive"))
      (node (ref "IC7") (pin "4") (pinfunction "VCC−_4") (pintype "passive"))
      (node (ref "IC8") (pin "5") (pinfunction "GND_5") (pintype "passive"))
      (node (ref "LED4") (pin "2") (pinfunction "K_2") (pintype "passive"))
      (node (ref "LED5") (pin "2") (pinfunction "K_2") (pintype "passive"))
      (node (ref "M3") (pin "2") (pinfunction "GND_2") (pintype "passive"))
      (node (ref "M3") (pin "4") (pinfunction "GND_4") (pintype "passive"))
      (node (ref "P11") (pin "2") (pinfunction "2_2") (pintype "passive"))
      (node (ref "P14") (pin "2") (pinfunction "2_2") (pintype "passive"))
      (node (ref "P8") (pin "2") (pinfunction "2_2") (pintype "passive"))
      (node (ref "R31") (pin "1") (pinfunction "1_1") (pintype "passive"))
      (node (ref "R32") (pin "1") (pinfunction "1_1") (pintype "passive"))
      (node (ref "R38") (pin "2") (pinfunction "2_2") (pintype "passive"))
      (node (ref "R39") (pin "2") (pinfunction "2_2") (pintype "passive"))
      (node (ref "R40") (pin "1") (pinfunction "1_1") (pintype "passive"))
      (node (ref "R43") (pin "1") (pinfunction "1_1") (pintype "passive"))
      (node (ref "R54") (pin "2") (pinfunction "2_2") (pintype "passive"))
      (node (ref "R57") (pin "2") (pinfunction "2_2") (pintype "passive"))
      (node (ref "VDR1") (pin "2") (pinfunction "2_2") (pintype "passive"))
    )
    (net (code "27") (name "GNDA") (class "Default")
      (node (ref "C70") (pin "2") (pinfunction "-_2") (pintype "passive"))
      (node (ref "P9") (pin "2") (pinfunction "2_2") (pintype "passive"))
    )
    (net (code "28") (name "Net-(C31-+)") (class "Default")
      (node (ref "C31") (pin "1") (pinfunction "+_1") (pintype "passive"))
      (node (ref "IC2") (pin "3") (pinfunction "IN-_3") (pintype "passive"))
      (node (ref "R28") (pin "1") (pinfunction "1_1") (pintype "passive"))
      (node (ref "R32") (pin "2") (pinfunction "2_2") (pintype "passive"))
    )
    (net (code "29") (name "Net-(C36-+)") (class "Default")
      (node (ref "C36") (pin "1") (pinfunction "+_1") (pintype "passive"))
      (node (ref "C40") (pin "1") (pinfunction "+_1") (pintype "passive"))
      (node (ref "C48") (pin "2") (pinfunction "-_2") (pintype "passive"))
      (node (ref "IC3") (pin "15") (pinfunction "OUTA_15") (pintype "passive"))
    )
    (net (code "30") (name "Net-(C37-+)") (class "Default")
      (node (ref "C37") (pin "1") (pinfunction "+_1") (pintype "passive"))
      (node (ref "C44") (pin "1") (pinfunction "+_1") (pintype "passive"))
      (node (ref "C49") (pin "2") (pinfunction "-_2") (pintype "passive"))
      (node (ref "IC4") (pin "15") (pinfunction "OUTA_15") (pintype "passive"))
    )
    (net (code "31") (name "Net-(C38-+)") (class "Default")
      (node (ref "C38") (pin "1") (pinfunction "+_1") (pintype "passive"))
      (node (ref "IC3") (pin "1") (pinfunction "INA_1") (pintype "passive"))
      (node (ref "R34") (pin "1") (pinfunction "1_1") (pintype "passive"))
    )
    (net (code "32") (name "Net-(C39-+)") (class "Default")
      (node (ref "C39") (pin "1") (pinfunction "+_1") (pintype "passive"))
      (node (ref "IC4") (pin "1") (pinfunction "INA_1") (pintype "passive"))
      (node (ref "R35") (pin "1") (pinfunction "1_1") (pintype "passive"))
    )
    (net (code "33") (name "Net-(C50-+)") (class "Default")
      (node (ref "C50") (pin "1") (pinfunction "+_1") (pintype "passive"))
      (node (ref "IC3") (pin "2") (pinfunction "INB_2") (pintype "passive"))
      (node (ref "R36") (pin "1") (pinfunction "1_1") (pintype "passive"))
    )
    (net (code "34") (name "Net-(C51-+)") (class "Default")
      (node (ref "C51") (pin "1") (pinfunction "+_1") (pintype "passive"))
      (node (ref "IC4") (pin "2") (pinfunction "INB_2") (pintype "passive"))
      (node (ref "R37") (pin "1") (pinfunction "1_1") (pintype "passive"))
    )
    (net (code "35") (name "Net-(C63--)") (class "Default")
      (node (ref "C63") (pin "2") (pinfunction "-_2") (pintype "passive"))
      (node (ref "IC5") (pin "2") (pinfunction "IN+_2") (pintype "passive"))
      (node (ref "R42") (pin "2") (pinfunction "2_2") (pintype "passive"))
      (node (ref "R47") (pin "1") (pinfunction "1_1") (pintype "passive"))
    )
    (net (code "36") (name "Net-(C64--)") (class "Default")
      (node (ref "C64") (pin "2") (pinfunction "-_2") (pintype "passive"))
      (node (ref "IC7") (pin "2") (pinfunction "IN+_2") (pintype "passive"))
      (node (ref "R41") (pin "2") (pinfunction "2_2") (pintype "passive"))
      (node (ref "R48") (pin "1") (pinfunction "1_1") (pintype "passive"))
    )
    (net (code "37") (name "Net-(C66-+)") (class "Default")
      (node (ref "C66") (pin "1") (pinfunction "+_1") (pintype "passive"))
      (node (ref "IC5") (pin "3") (pinfunction "IN-_3") (pintype "passive"))
      (node (ref "R52") (pin "1") (pinfunction "1_1") (pintype "passive"))
    )
    (net (code "38") (name "Net-(C69-+)") (class "Default")
      (node (ref "C69") (pin "1") (pinfunction "+_1") (pintype "passive"))
      (node (ref "IC6") (pin "4") (pinfunction "4_4") (pintype "passive"))
      (node (ref "R48") (pin "2") (pinfunction "2_2") (pintype "passive"))
      (node (ref "R55") (pin "2") (pinfunction "2_2") (pintype "passive"))
    )
    (net (code "39") (name "Net-(C69--)") (class "Default")
      (node (ref "C69") (pin "2") (pinfunction "-_2") (pintype "passive"))
      (node (ref "IC6") (pin "3") (pinfunction "3_3") (pintype "passive"))
      (node (ref "R53") (pin "1") (pinfunction "1_1") (pintype "passive"))
      (node (ref "R55") (pin "1") (pinfunction "1_1") (pintype "passive"))
    )
    (net (code "40") (name "Net-(D8-A)") (class "Default")
      (node (ref "D8") (pin "1") (pinfunction "A_1") (pintype "passive"))
      (node (ref "Q4") (pin "1") (pinfunction "G_1") (pintype "passive"))
      (node (ref "R31") (pin "2") (pinfunction "2_2") (pintype "passive"))
    )
    (net (code "41") (name "Net-(IC2-BALANCE)") (class "Default")
      (node (ref "IC2") (pin "5") (pinfunction "BALANCE_5") (pintype "passive"))
      (node (ref "IC2") (pin "6") (pinfunction "BAL/STRB_6") (pintype "passive"))
    )
    (net (code "42") (name "Net-(IC5-BALANCE)") (class "Default")
      (node (ref "IC5") (pin "5") (pinfunction "BALANCE_5") (pintype "passive"))
      (node (ref "IC5") (pin "6") (pinfunction "BAL/STRB_6") (pintype "passive"))
    )
    (net (code "43") (name "Net-(IC6-Pad1)") (class "Default")
      (node (ref "IC6") (pin "1") (pinfunction "1_1") (pintype "passive"))
      (node (ref "R43") (pin "2") (pinfunction "2_2") (pintype "passive"))
      (node (ref "R46") (pin "1") (pinfunction "1_1") (pintype "passive"))
    )
    (net (code "44") (name "Net-(IC6-Pad2)") (class "Default")
      (node (ref "IC6") (pin "2") (pinfunction "2_2") (pintype "passive"))
      (node (ref "R56") (pin "2") (pinfunction "2_2") (pintype "passive"))
      (node (ref "R57") (pin "1") (pinfunction "1_1") (pintype "passive"))
    )
    (net (code "45") (name "Net-(IC7-BALANCE)") (class "Default")
      (node (ref "IC7") (pin "5") (pinfunction "BALANCE_5") (pintype "passive"))
      (node (ref "IC7") (pin "6") (pinfunction "BAL/STRB_6") (pintype "passive"))
    )
    (net (code "46") (name "Net-(IC7-IN-)") (class "Default")
      (node (ref "IC7") (pin "3") (pinfunction "IN-_3") (pintype "passive"))
      (node (ref "R50") (pin "1") (pinfunction "1_1") (pintype "passive"))
      (node (ref "R54") (pin "1") (pinfunction "1_1") (pintype "passive"))
    )
    (net (code "47") (name "Net-(LED4-A)") (class "Default")
      (node (ref "LED4") (pin "1") (pinfunction "A_1") (pintype "passive"))
      (node (ref "R29") (pin "1") (pinfunction "1_1") (pintype "passive"))
    )
    (net (code "48") (name "Net-(LED5-A)") (class "Default")
      (node (ref "LED5") (pin "1") (pinfunction "A_1") (pintype "passive"))
      (node (ref "R33") (pin "1") (pinfunction "1_1") (pintype "passive"))
    )
    (net (code "49") (name "Net-(P9-Pad1)") (class "Default")
      (node (ref "P9") (pin "1") (pinfunction "1_1") (pintype "passive"))
      (node (ref "R58") (pin "1") (pinfunction "1_1") (pintype "passive"))
    )
    (net (code "50") (name "Net-(Q4-D)") (class "Default")
      (node (ref "D9") (pin "2") (pinfunction "2_2") (pintype "passive"))
      (node (ref "F1") (pin "2") (pinfunction "2_2") (pintype "passive"))
      (node (ref "Q4") (pin "2") (pinfunction "D_2") (pintype "passive"))
      (node (ref "VDR1") (pin "1") (pinfunction "1_1") (pintype "passive"))
    )
    (net (code "51") (name "unconnected-(IC3-NC-Pad7)") (class "Default")
      (node (ref "IC3") (pin "7") (pinfunction "NC_7") (pintype "passive+no_connect"))
    )
    (net (code "52") (name "unconnected-(IC3-NC-Pad12)") (class "Default")
      (node (ref "IC3") (pin "12") (pinfunction "NC_12") (pintype "passive+no_connect"))
    )
    (net (code "53") (name "unconnected-(IC3-NC-Pad13)") (class "Default")
      (node (ref "IC3") (pin "13") (pinfunction "NC_13") (pintype "passive+no_connect"))
    )
    (net (code "54") (name "unconnected-(IC4-NC-Pad7)") (class "Default")
      (node (ref "IC4") (pin "7") (pinfunction "NC_7") (pintype "passive+no_connect"))
    )
    (net (code "55") (name "unconnected-(IC4-NC-Pad12)") (class "Default")
      (node (ref "IC4") (pin "12") (pinfunction "NC_12") (pintype "passive+no_connect"))
    )
    (net (code "56") (name "unconnected-(IC4-NC-Pad13)") (class "Default")
      (node (ref "IC4") (pin "13") (pinfunction "NC_13") (pintype "passive+no_connect"))
    )
    (net (code "57") (name "unconnected-(IC8-NC-Pad1)") (class "Default")
      (node (ref "IC8") (pin "1") (pinfunction "NC_1") (pintype "passive+no_connect"))
    )
    (net (code "58") (name "unconnected-(IC8-NC-Pad4)") (class "Default")
      (node (ref "IC8") (pin "4") (pinfunction "NC_4") (pintype "passive+no_connect"))
    )
  )
)
